# XBeeThermSMD.net
KiCad netlist of a schematic drawn in EAGLE
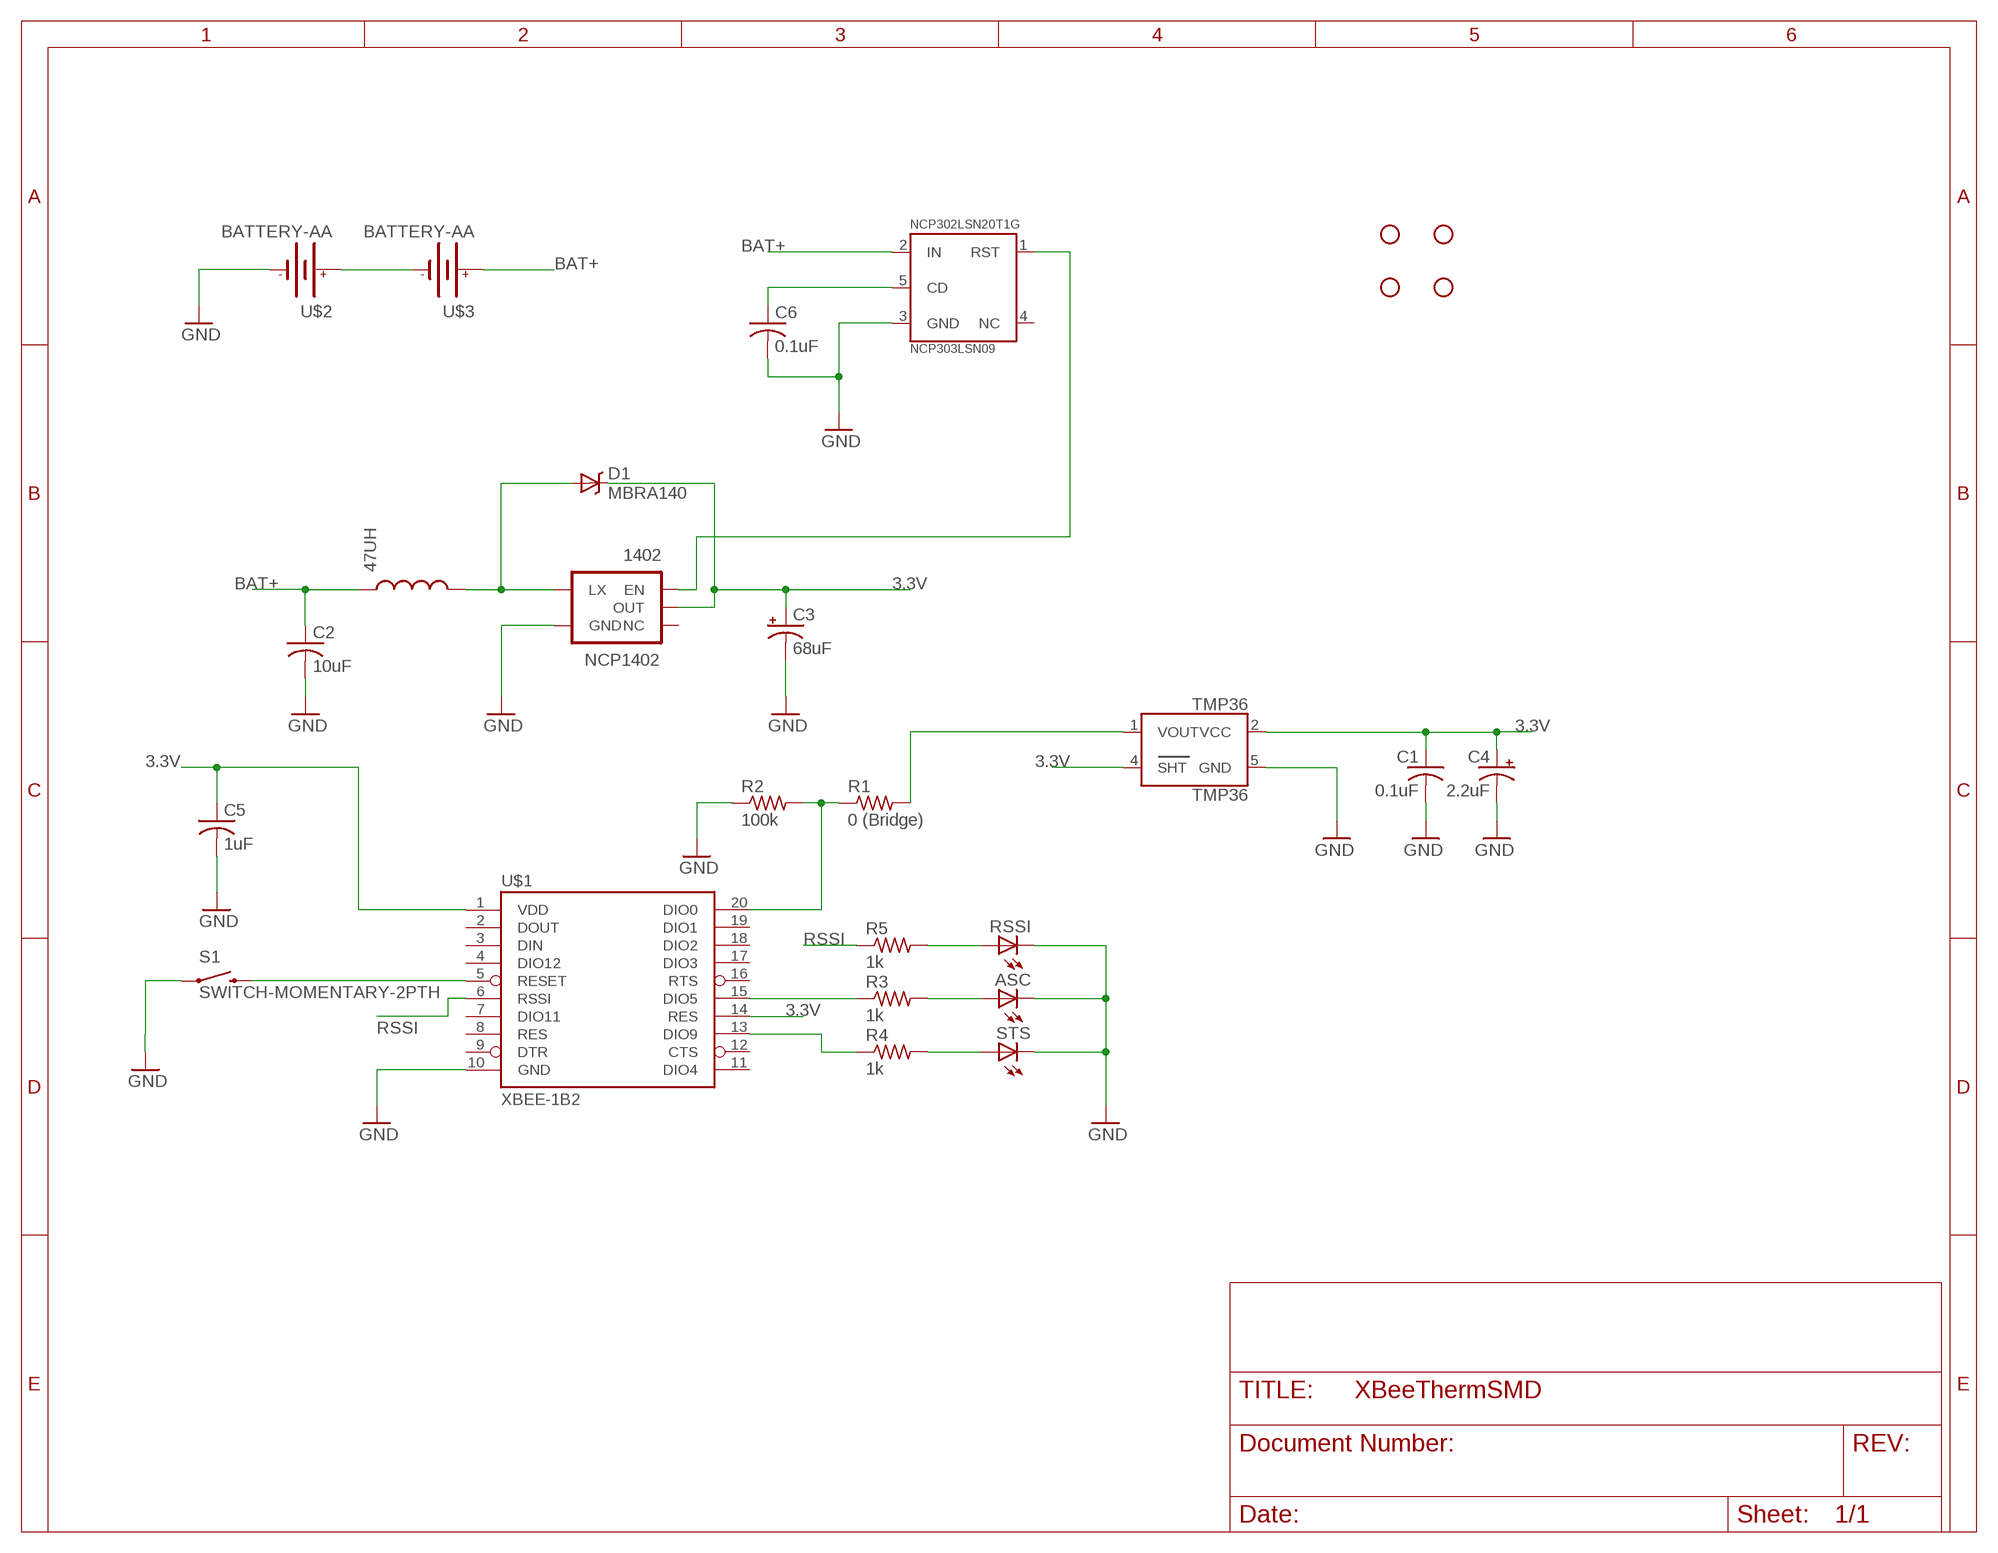
[diagram p0: schematic, sheet 1]

(export (version "E")
  (design (tool "Eeschema 10.0.6"))
  (components
    (comp (ref "47UH")
      (value "INDUCTORCR54")
      (footprint "eagle-import:CR54")
      (libsource (lib "eagle-import") (part "INDUCTORCR54"))
    )
    (comp (ref "1402")
      (value "NCP1402")
      (footprint "eagle-import:SOT23-5")
      (libsource (lib "eagle-import") (part "V_REG_NCP1400SOT23-5"))
    )
    (comp (ref "ASC")
      (value "LEDCHIP-LED0603")
      (footprint "eagle-import:CHIP-LED0603")
      (libsource (lib "eagle-import") (part "LEDCHIP-LED0603"))
    )
    (comp (ref "C1")
      (value "0.1uF")
      (footprint "eagle-import:C0402")
      (libsource (lib "eagle-import") (part "resistor_C-USC0402"))
    )
    (comp (ref "C2")
      (value "10uF")
      (footprint "eagle-import:C0805")
      (libsource (lib "eagle-import") (part "resistor_C-USC0805"))
    )
    (comp (ref "C3")
      (value "68uF")
      (footprint "eagle-import:CT3216")
      (libsource (lib "eagle-import") (part "CPOL-USCT3216"))
    )
    (comp (ref "C4")
      (value "2.2uF")
      (footprint "eagle-import:R_2012-12R")
      (libsource (lib "eagle-import") (part "CPOL-USR/2012-12R"))
    )
    (comp (ref "C5")
      (value "1uF")
      (footprint "eagle-import:C0805")
      (libsource (lib "eagle-import") (part "resistor_C-USC0805"))
    )
    (comp (ref "C6")
      (value "0.1uF")
      (footprint "eagle-import:C0402")
      (libsource (lib "eagle-import") (part "C-USC0402"))
    )
    (comp (ref "D1")
      (value "MBRA140")
      (footprint "eagle-import:SMA-DIODE")
      (libsource (lib "eagle-import") (part "MBRA140"))
    )
    (comp (ref "NCP302LSN20T1G")
      (value "NCP303LSN09")
      (footprint "eagle-import:SOT23-5")
      (libsource (lib "eagle-import") (part "NCP303LSN09"))
    )
    (comp (ref "R1")
      (value "0 (Bridge)")
      (footprint "eagle-import:R0603")
      (libsource (lib "eagle-import") (part "R-US_R0603"))
    )
    (comp (ref "R2")
      (value "100k")
      (footprint "eagle-import:R0603")
      (libsource (lib "eagle-import") (part "R-US_R0603"))
    )
    (comp (ref "R3")
      (value "1k")
      (footprint "eagle-import:R0603")
      (libsource (lib "eagle-import") (part "R-US_R0603"))
    )
    (comp (ref "R4")
      (value "1k")
      (footprint "eagle-import:R0603")
      (libsource (lib "eagle-import") (part "R-US_R0603"))
    )
    (comp (ref "R5")
      (value "1k")
      (footprint "eagle-import:R0603")
      (libsource (lib "eagle-import") (part "R-US_R0603"))
    )
    (comp (ref "RSSI")
      (value "LEDCHIP-LED0603")
      (footprint "eagle-import:CHIP-LED0603")
      (libsource (lib "eagle-import") (part "LEDCHIP-LED0603"))
    )
    (comp (ref "S1")
      (value "SWITCH-MOMENTARY-2PTH")
      (footprint "eagle-import:TACTILE-PTH")
      (libsource (lib "eagle-import") (part "SWITCH-MOMENTARY-2PTH"))
    )
    (comp (ref "STANDOFF1")
      (value "STAND-OFF")
      (footprint "eagle-import:STAND-OFF")
      (libsource (lib "eagle-import") (part "STAND-OFF"))
    )
    (comp (ref "STANDOFF2")
      (value "STAND-OFF")
      (footprint "eagle-import:STAND-OFF")
      (libsource (lib "eagle-import") (part "STAND-OFF"))
    )
    (comp (ref "STANDOFF3")
      (value "STAND-OFF")
      (footprint "eagle-import:STAND-OFF")
      (libsource (lib "eagle-import") (part "STAND-OFF"))
    )
    (comp (ref "STANDOFF4")
      (value "STAND-OFF")
      (footprint "eagle-import:STAND-OFF")
      (libsource (lib "eagle-import") (part "STAND-OFF"))
    )
    (comp (ref "STS")
      (value "LEDCHIP-LED0603")
      (footprint "eagle-import:CHIP-LED0603")
      (libsource (lib "eagle-import") (part "LEDCHIP-LED0603"))
    )
    (comp (ref "TMP36")
      (value "TMP36")
      (footprint "eagle-import:SOT23-5")
      (libsource (lib "eagle-import") (part "TMP36"))
    )
    (comp (ref "U$1")
      (value "XBEE-1B2")
      (footprint "eagle-import:XBEE-SILK")
      (libsource (lib "eagle-import") (part "XBEE-1B2"))
    )
    (comp (ref "U$2")
      (value "BATTERY-AA")
      (footprint "eagle-import:BATTERY_AA_CLIPS")
      (libsource (lib "eagle-import") (part "BATTERY-AA"))
    )
    (comp (ref "U$3")
      (value "BATTERY-AA")
      (footprint "eagle-import:BATTERY_AA_CLIPS")
      (libsource (lib "eagle-import") (part "BATTERY-AA"))
    )
  )
  (nets
    (net (code "1") (name "/3.3V") (class "Default")
      (node (ref "1402") (pin "2") (pinfunction "OUT_2") (pintype "passive"))
      (node (ref "C1") (pin "1") (pinfunction "1_1") (pintype "passive"))
      (node (ref "C3") (pin "+") (pinfunction "+_+") (pintype "passive"))
      (node (ref "C4") (pin "+") (pinfunction "+_+") (pintype "passive"))
      (node (ref "C5") (pin "1") (pinfunction "1_1") (pintype "passive"))
      (node (ref "D1") (pin "C") (pinfunction "C_C") (pintype "passive"))
      (node (ref "TMP36") (pin "2") (pinfunction "VCC_2") (pintype "bidirectional"))
      (node (ref "TMP36") (pin "4") (pinfunction "SHT_4") (pintype "bidirectional"))
      (node (ref "U$1") (pin "1") (pinfunction "VDD_1") (pintype "power_in"))
      (node (ref "U$1") (pin "14") (pinfunction "RES_14") (pintype "bidirectional"))
    )
    (net (code "2") (name "/BAT+") (class "Default")
      (node (ref "47UH") (pin "P$1") (pinfunction "1_P$1") (pintype "passive"))
      (node (ref "C2") (pin "1") (pinfunction "1_1") (pintype "passive"))
      (node (ref "NCP302LSN20T1G") (pin "2") (pinfunction "IN_2") (pintype "bidirectional"))
      (node (ref "U$3") (pin "PWR@1") (pinfunction "+_PWR@1") (pintype "power_in"))
      (node (ref "U$3") (pin "PWR@2") (pinfunction "+_PWR@2") (pintype "power_in"))
    )
    (net (code "3") (name "/RSSI") (class "Default")
      (node (ref "R5") (pin "1") (pinfunction "1_1") (pintype "passive"))
      (node (ref "U$1") (pin "6") (pinfunction "RSSI_6") (pintype "bidirectional"))
    )
    (net (code "4") (name "GND") (class "Default")
      (node (ref "1402") (pin "4") (pinfunction "GND_4") (pintype "input"))
      (node (ref "ASC") (pin "C") (pinfunction "C_C") (pintype "passive"))
      (node (ref "C1") (pin "2") (pinfunction "2_2") (pintype "passive"))
      (node (ref "C2") (pin "2") (pinfunction "2_2") (pintype "passive"))
      (node (ref "C3") (pin "-") (pinfunction "-_-") (pintype "passive"))
      (node (ref "C4") (pin "-") (pinfunction "-_-") (pintype "passive"))
      (node (ref "C5") (pin "2") (pinfunction "2_2") (pintype "passive"))
      (node (ref "C6") (pin "2") (pinfunction "2_2") (pintype "passive"))
      (node (ref "NCP302LSN20T1G") (pin "3") (pinfunction "GND_3") (pintype "bidirectional"))
      (node (ref "R2") (pin "1") (pinfunction "1_1") (pintype "passive"))
      (node (ref "RSSI") (pin "C") (pinfunction "C_C") (pintype "passive"))
      (node (ref "S1") (pin "1") (pinfunction "1_1") (pintype "passive"))
      (node (ref "STS") (pin "C") (pinfunction "C_C") (pintype "passive"))
      (node (ref "TMP36") (pin "5") (pinfunction "GND_5") (pintype "bidirectional"))
      (node (ref "U$1") (pin "10") (pinfunction "GND_10") (pintype "power_in"))
      (node (ref "U$2") (pin "GND@1") (pinfunction "-_GND@1") (pintype "power_in"))
      (node (ref "U$2") (pin "GND@2") (pinfunction "-_GND@2") (pintype "power_in"))
    )
    (net (code "5") (name "Net-(1402-EN)") (class "Default")
      (node (ref "1402") (pin "1") (pinfunction "EN_1") (pintype "input"))
      (node (ref "NCP302LSN20T1G") (pin "1") (pinfunction "RST_1") (pintype "bidirectional"))
    )
    (net (code "6") (name "Net-(1402-LX)") (class "Default")
      (node (ref "1402") (pin "5") (pinfunction "LX_5") (pintype "input"))
      (node (ref "47UH") (pin "P$2") (pinfunction "2_P$2") (pintype "passive"))
      (node (ref "D1") (pin "A") (pinfunction "A_A") (pintype "passive"))
    )
    (net (code "7") (name "Net-(ASC-PadA)") (class "Default")
      (node (ref "ASC") (pin "A") (pinfunction "A_A") (pintype "passive"))
      (node (ref "R3") (pin "2") (pinfunction "2_2") (pintype "passive"))
    )
    (net (code "8") (name "Net-(NCP302LSN20T1G-CD)") (class "Default")
      (node (ref "C6") (pin "1") (pinfunction "1_1") (pintype "passive"))
      (node (ref "NCP302LSN20T1G") (pin "5") (pinfunction "CD_5") (pintype "bidirectional"))
    )
    (net (code "9") (name "Net-(R4-Pad2)") (class "Default")
      (node (ref "R4") (pin "2") (pinfunction "2_2") (pintype "passive"))
      (node (ref "STS") (pin "A") (pinfunction "A_A") (pintype "passive"))
    )
    (net (code "10") (name "Net-(R5-Pad2)") (class "Default")
      (node (ref "R5") (pin "2") (pinfunction "2_2") (pintype "passive"))
      (node (ref "RSSI") (pin "A") (pinfunction "A_A") (pintype "passive"))
    )
    (net (code "11") (name "Net-(S1-2)") (class "Default")
      (node (ref "S1") (pin "3") (pinfunction "2_3") (pintype "passive"))
      (node (ref "U$1") (pin "5") (pinfunction "RESET_5") (pintype "input"))
    )
    (net (code "12") (name "Net-(TMP36-VOUT)") (class "Default")
      (node (ref "R1") (pin "2") (pinfunction "2_2") (pintype "passive"))
      (node (ref "TMP36") (pin "1") (pinfunction "VOUT_1") (pintype "bidirectional"))
    )
    (net (code "13") (name "Net-(U$1-DIO0)") (class "Default")
      (node (ref "R1") (pin "1") (pinfunction "1_1") (pintype "passive"))
      (node (ref "R2") (pin "2") (pinfunction "2_2") (pintype "passive"))
      (node (ref "U$1") (pin "20") (pinfunction "DIO0_20") (pintype "bidirectional"))
    )
    (net (code "14") (name "Net-(U$1-DIO5)") (class "Default")
      (node (ref "R3") (pin "1") (pinfunction "1_1") (pintype "passive"))
      (node (ref "U$1") (pin "15") (pinfunction "DIO5_15") (pintype "bidirectional"))
    )
    (net (code "15") (name "Net-(U$1-DIO9)") (class "Default")
      (node (ref "R4") (pin "1") (pinfunction "1_1") (pintype "passive"))
      (node (ref "U$1") (pin "13") (pinfunction "DIO9_13") (pintype "bidirectional"))
    )
    (net (code "16") (name "Net-(U$2-+-PadPWR@1)") (class "Default")
      (node (ref "U$2") (pin "PWR@1") (pinfunction "+_PWR@1") (pintype "power_in"))
      (node (ref "U$2") (pin "PWR@2") (pinfunction "+_PWR@2") (pintype "power_in"))
      (node (ref "U$3") (pin "GND@1") (pinfunction "-_GND@1") (pintype "power_in"))
      (node (ref "U$3") (pin "GND@2") (pinfunction "-_GND@2") (pintype "power_in"))
    )
    (net (code "17") (name "unconnected-(1402-NC-Pad3)") (class "Default")
      (node (ref "1402") (pin "3") (pinfunction "NC_3") (pintype "input"))
    )
    (net (code "18") (name "unconnected-(NCP302LSN20T1G-NC-Pad4)") (class "Default")
      (node (ref "NCP302LSN20T1G") (pin "4") (pinfunction "NC_4") (pintype "bidirectional"))
    )
    (net (code "19") (name "unconnected-(U$1-CTS-Pad12)") (class "Default")
      (node (ref "U$1") (pin "12") (pinfunction "CTS_12") (pintype "output"))
    )
    (net (code "20") (name "unconnected-(U$1-DIN-Pad3)") (class "Default")
      (node (ref "U$1") (pin "3") (pinfunction "DIN_3") (pintype "input"))
    )
    (net (code "21") (name "unconnected-(U$1-DIO1-Pad19)") (class "Default")
      (node (ref "U$1") (pin "19") (pinfunction "DIO1_19") (pintype "bidirectional"))
    )
    (net (code "22") (name "unconnected-(U$1-DIO2-Pad18)") (class "Default")
      (node (ref "U$1") (pin "18") (pinfunction "DIO2_18") (pintype "bidirectional"))
    )
    (net (code "23") (name "unconnected-(U$1-DIO3-Pad17)") (class "Default")
      (node (ref "U$1") (pin "17") (pinfunction "DIO3_17") (pintype "bidirectional"))
    )
    (net (code "24") (name "unconnected-(U$1-DIO4-Pad11)") (class "Default")
      (node (ref "U$1") (pin "11") (pinfunction "DIO4_11") (pintype "bidirectional"))
    )
    (net (code "25") (name "unconnected-(U$1-DIO11-Pad7)") (class "Default")
      (node (ref "U$1") (pin "7") (pinfunction "DIO11_7") (pintype "bidirectional"))
    )
    (net (code "26") (name "unconnected-(U$1-DIO12-Pad4)") (class "Default")
      (node (ref "U$1") (pin "4") (pinfunction "DIO12_4") (pintype "bidirectional"))
    )
    (net (code "27") (name "unconnected-(U$1-DOUT-Pad2)") (class "Default")
      (node (ref "U$1") (pin "2") (pinfunction "DOUT_2") (pintype "output"))
    )
    (net (code "28") (name "unconnected-(U$1-DTR-Pad9)") (class "Default")
      (node (ref "U$1") (pin "9") (pinfunction "DTR_9") (pintype "bidirectional"))
    )
    (net (code "29") (name "unconnected-(U$1-RES-Pad8)") (class "Default")
      (node (ref "U$1") (pin "8") (pinfunction "RES_8") (pintype "bidirectional"))
    )
    (net (code "30") (name "unconnected-(U$1-RTS-Pad16)") (class "Default")
      (node (ref "U$1") (pin "16") (pinfunction "RTS_16") (pintype "input"))
    )
  )
)
